# Trinket_TH_thru_parts_power_breakout.net
KiCad netlist of a schematic drawn in EAGLE
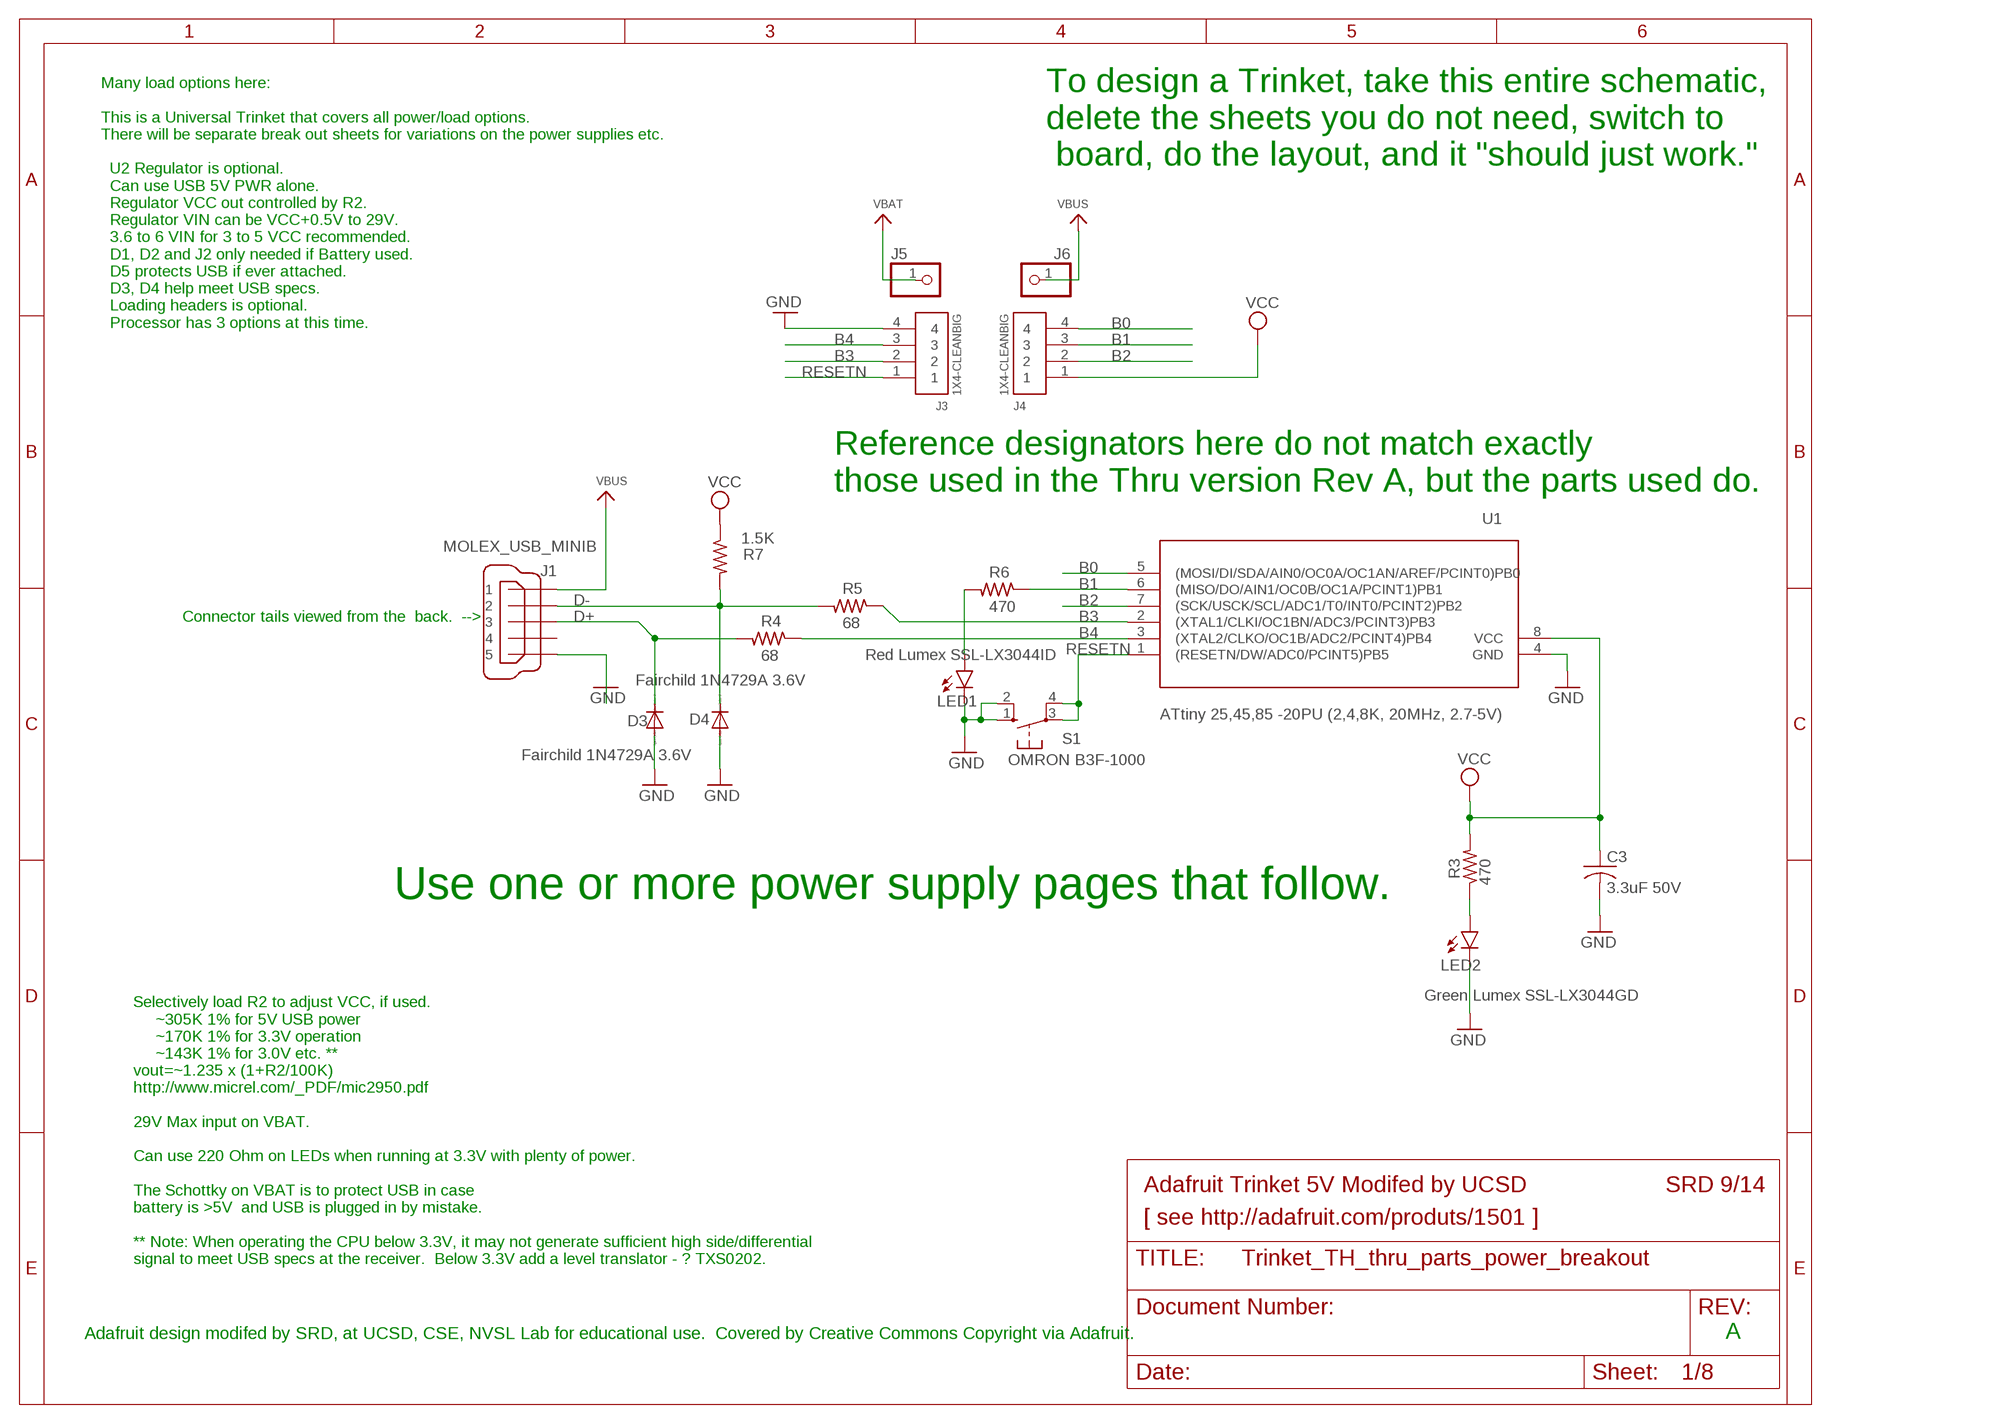
[diagram p0: schematic, sheet 1]
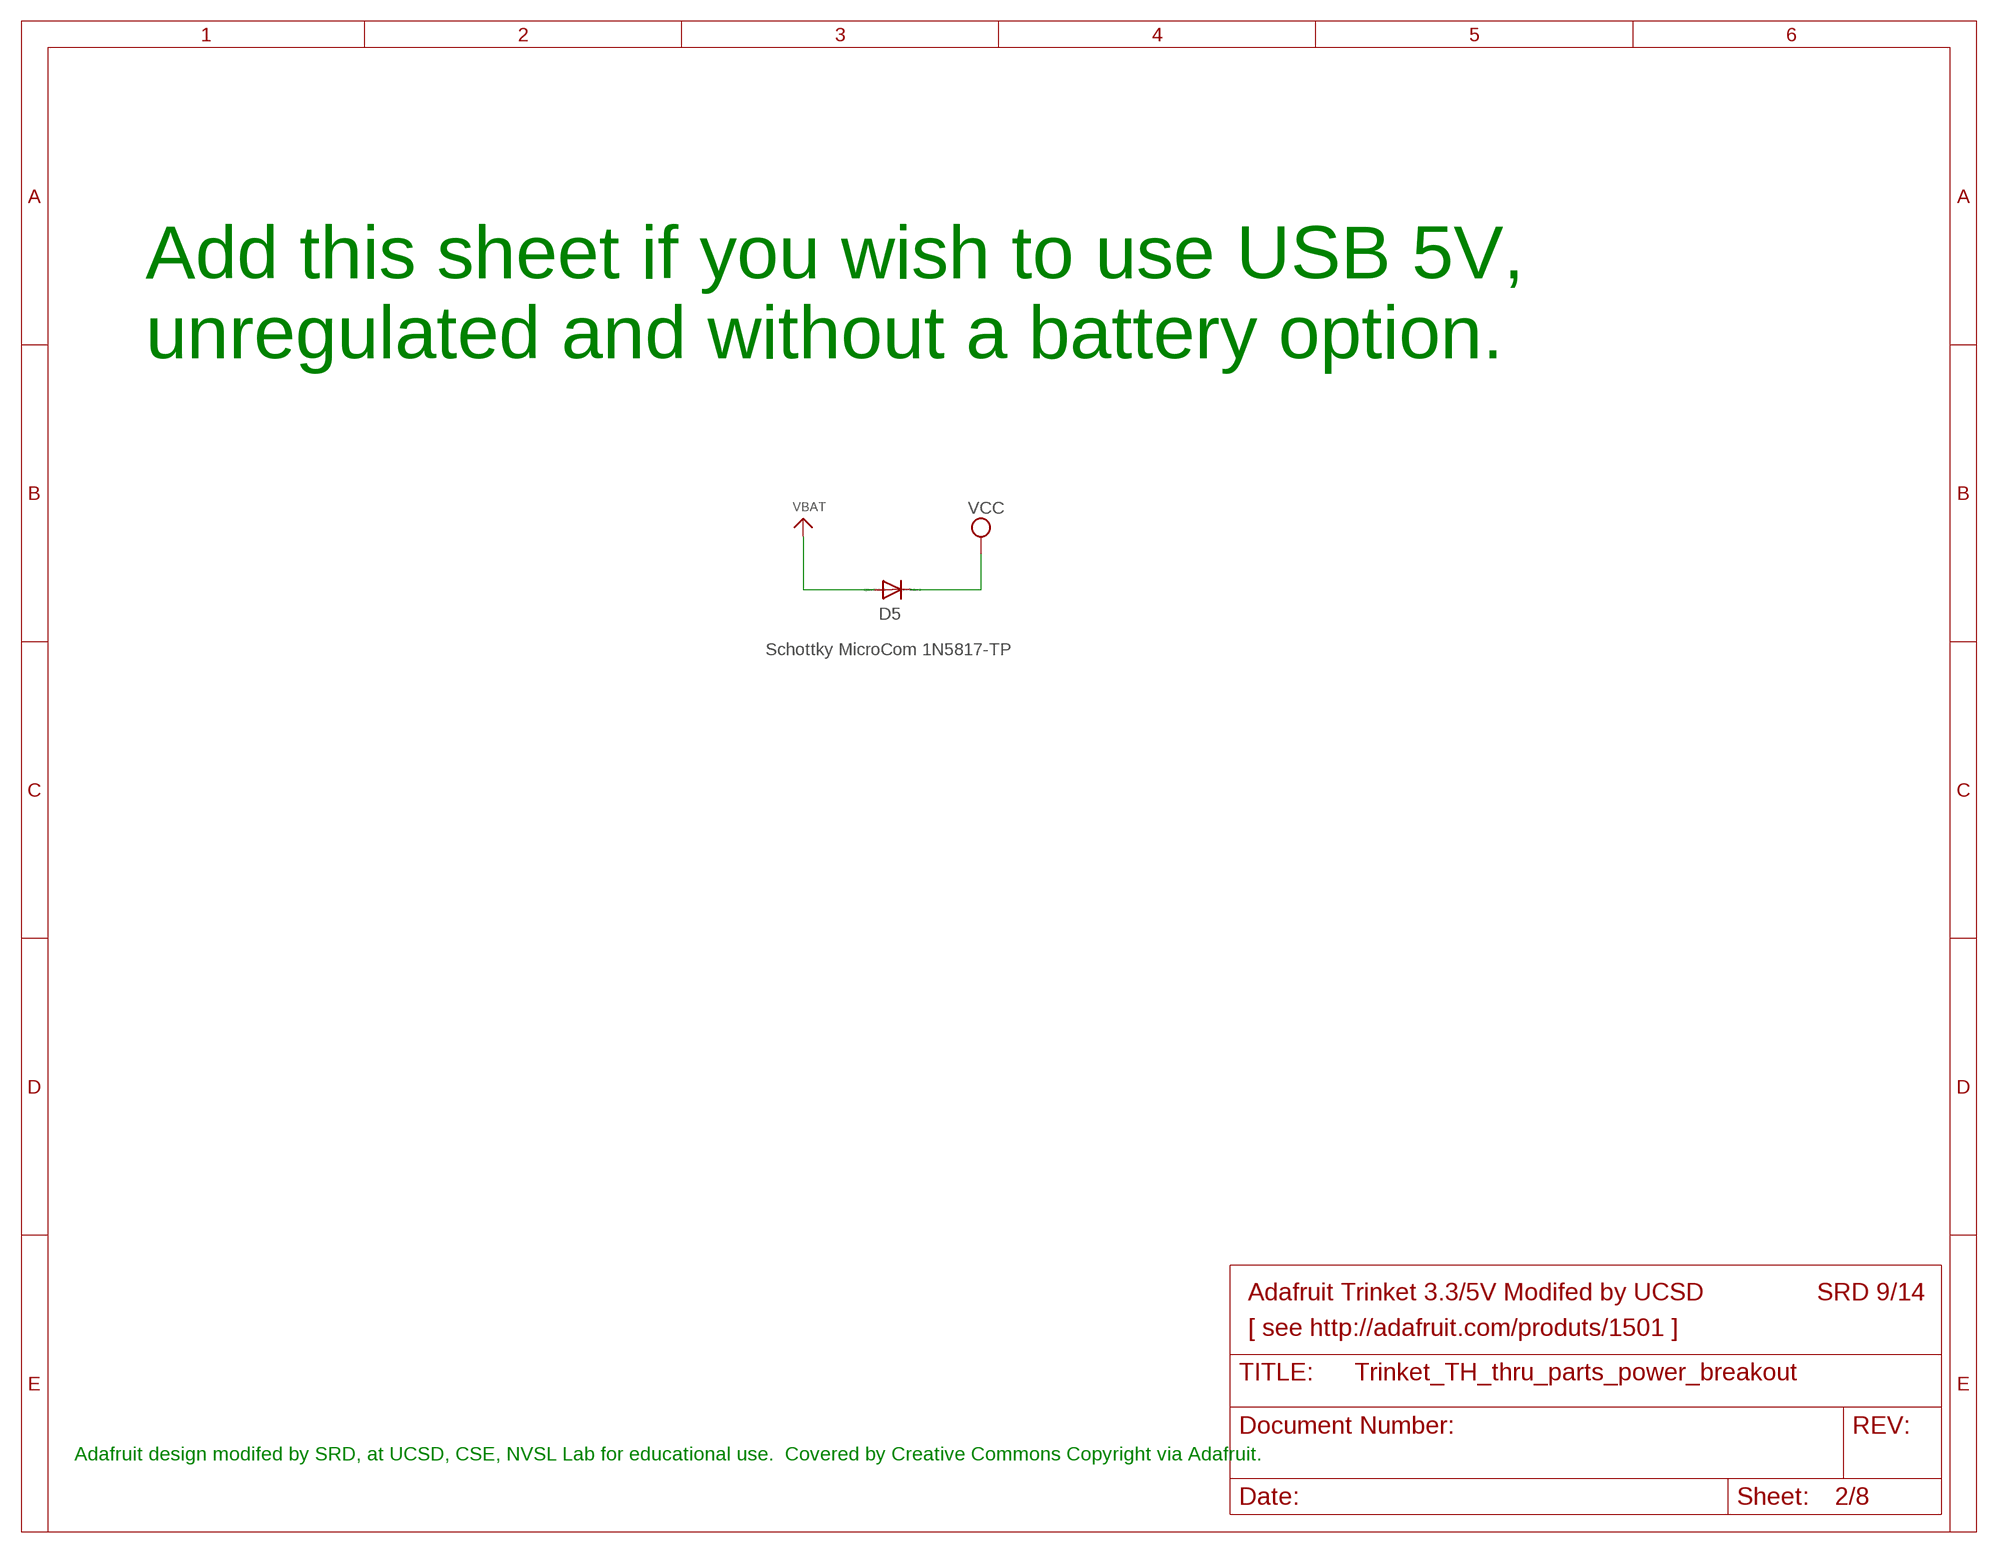
[diagram p1: schematic, sheet 2]
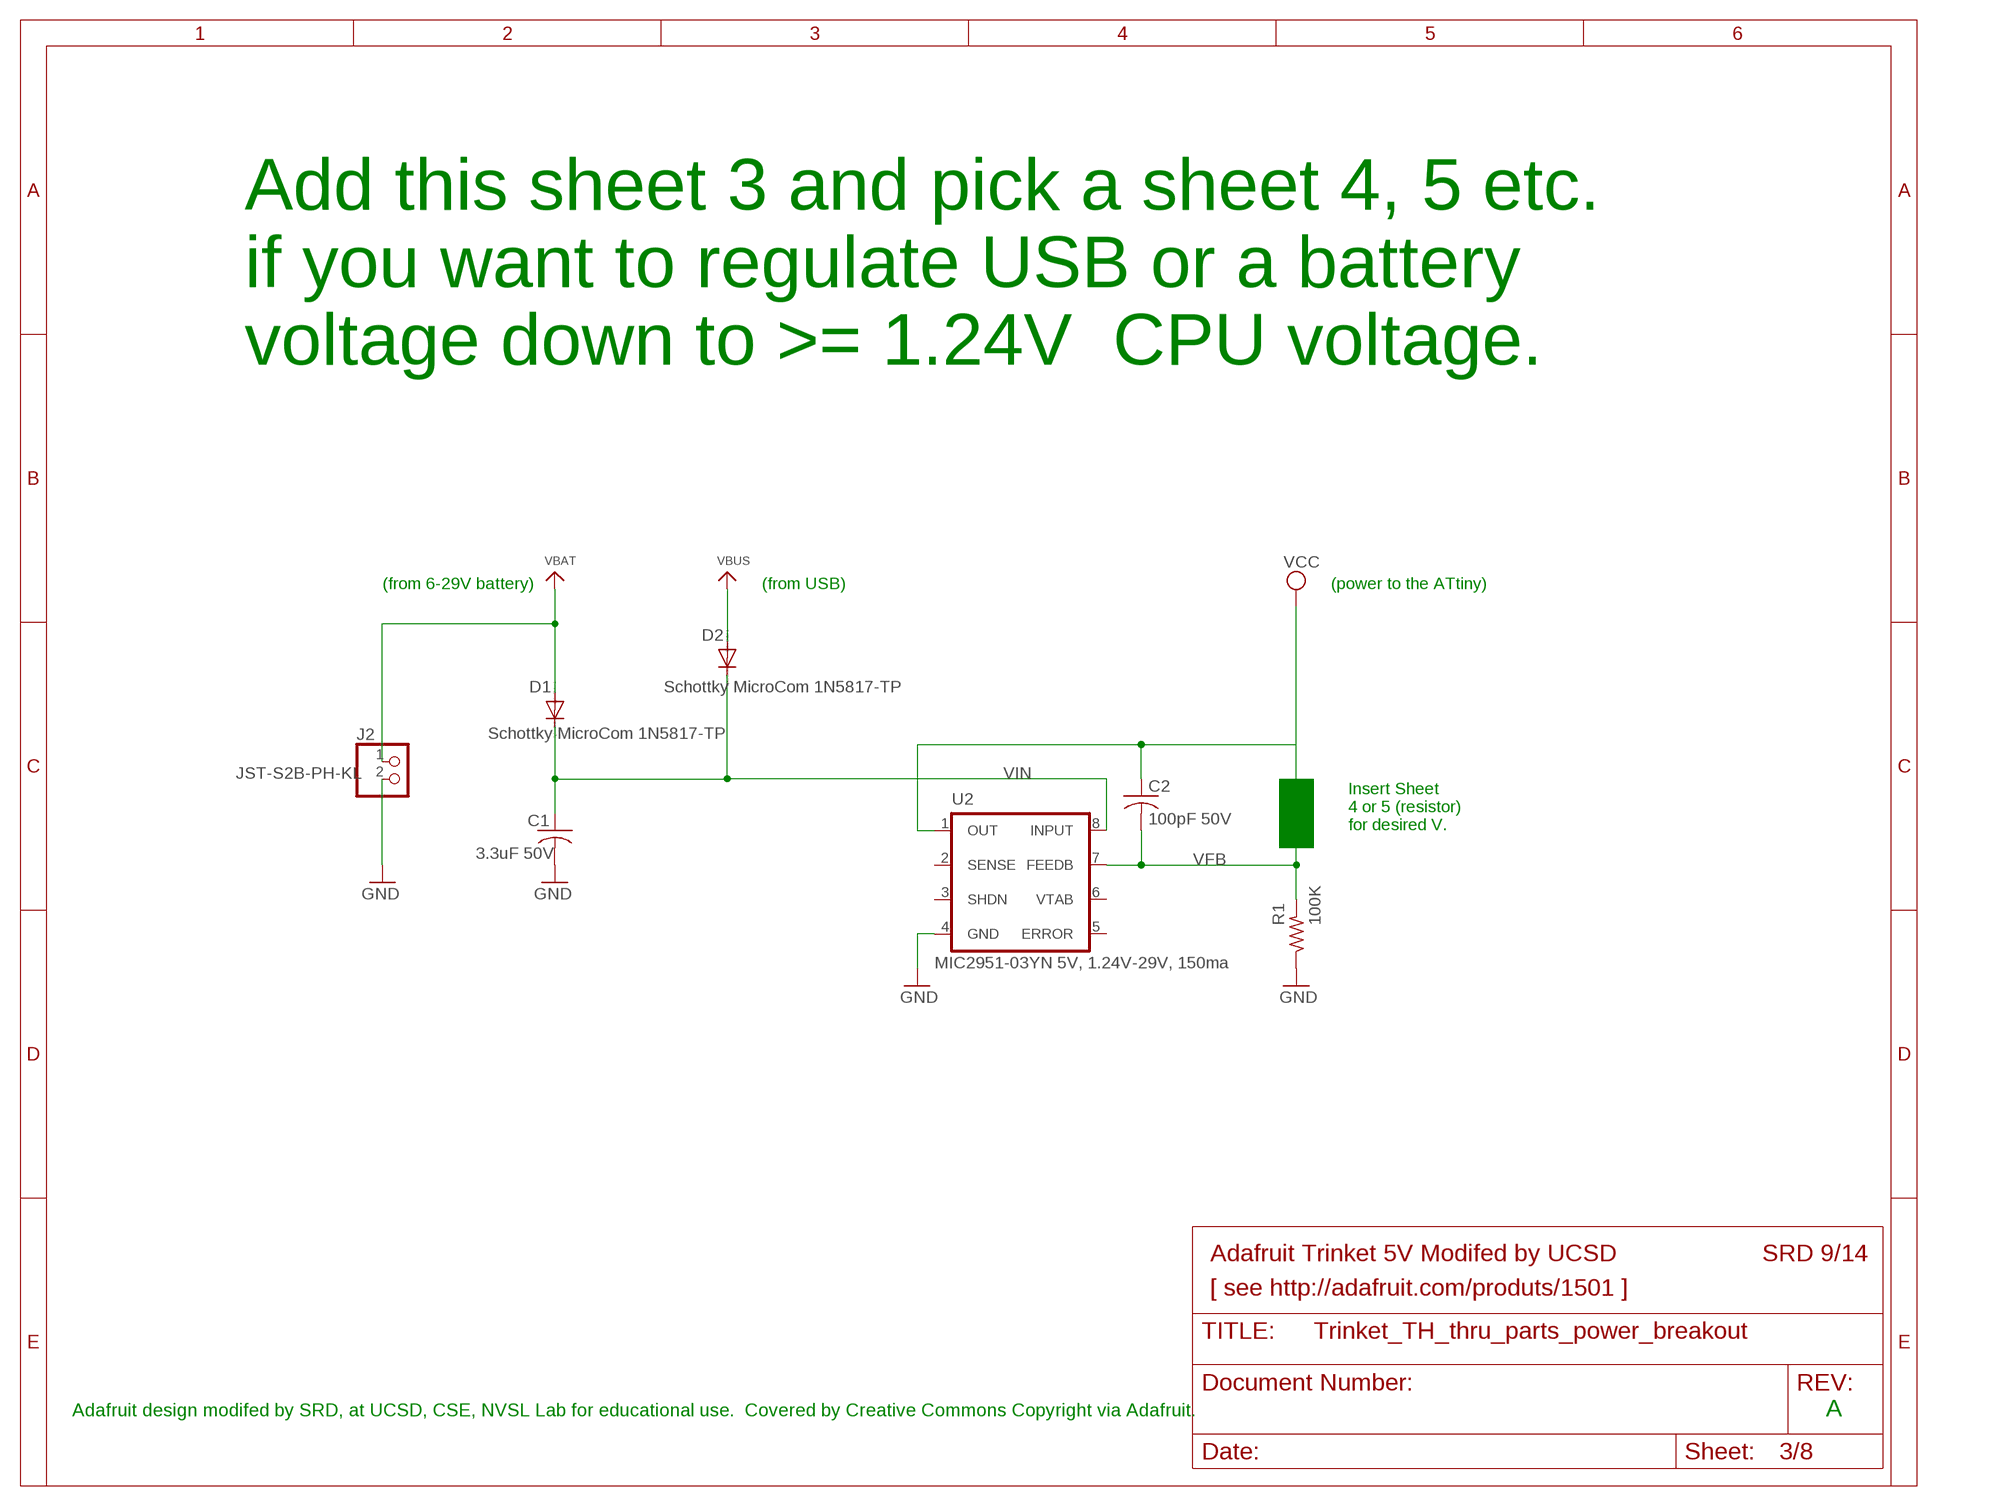
[diagram p2: schematic, sheet 3]
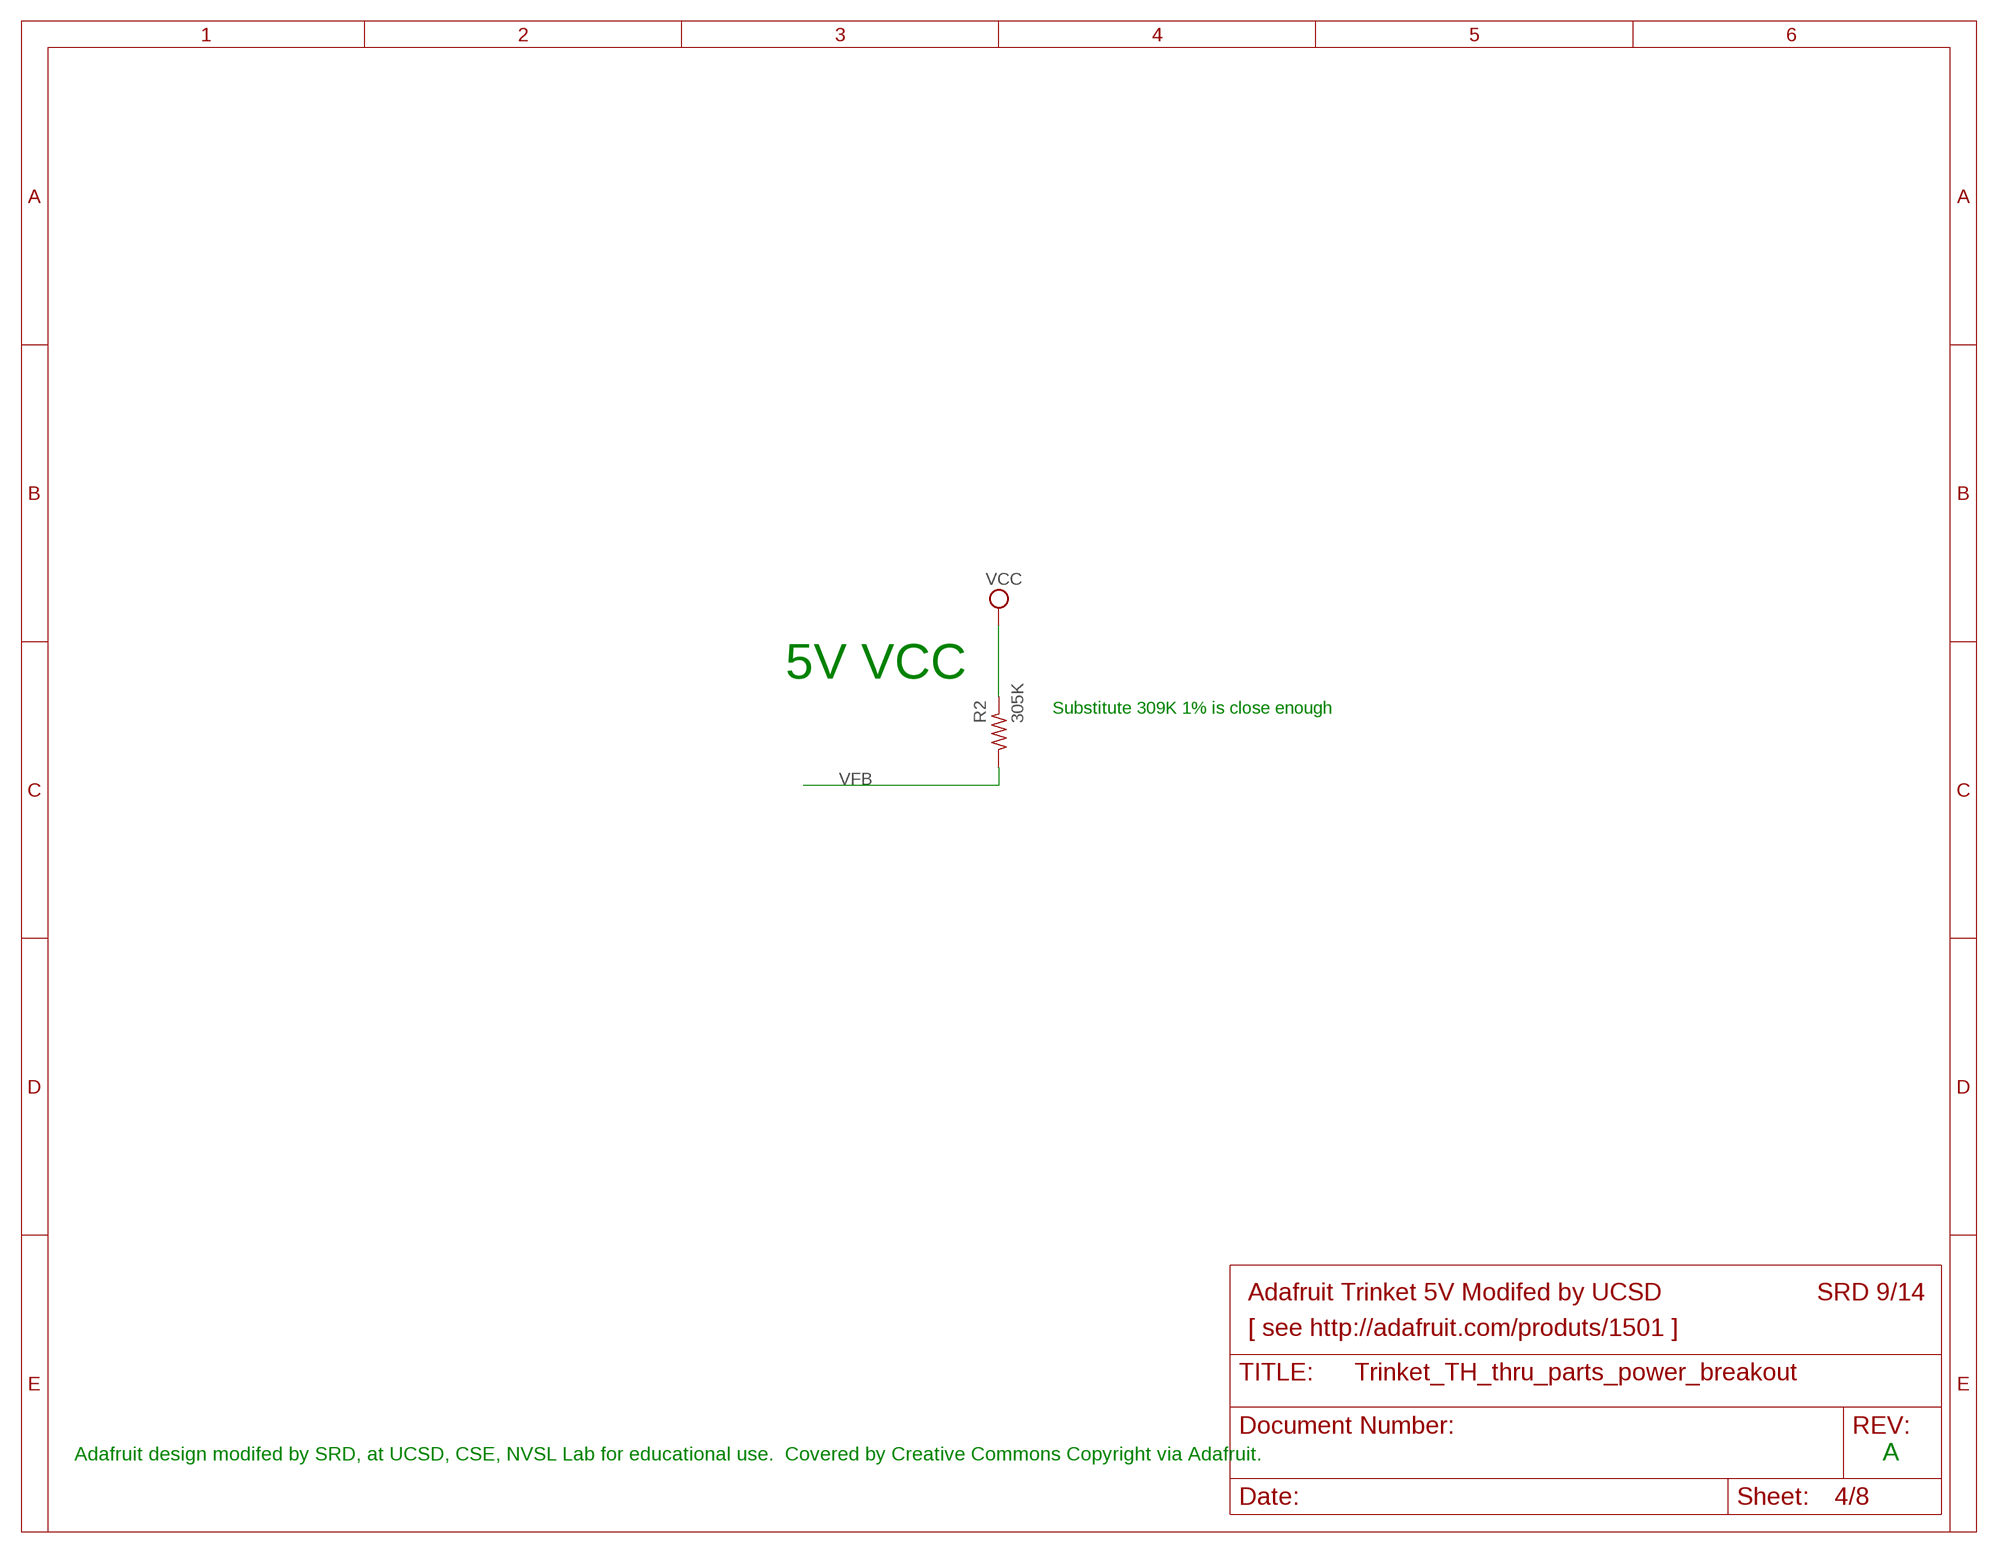
[diagram p3: schematic, sheet 4]
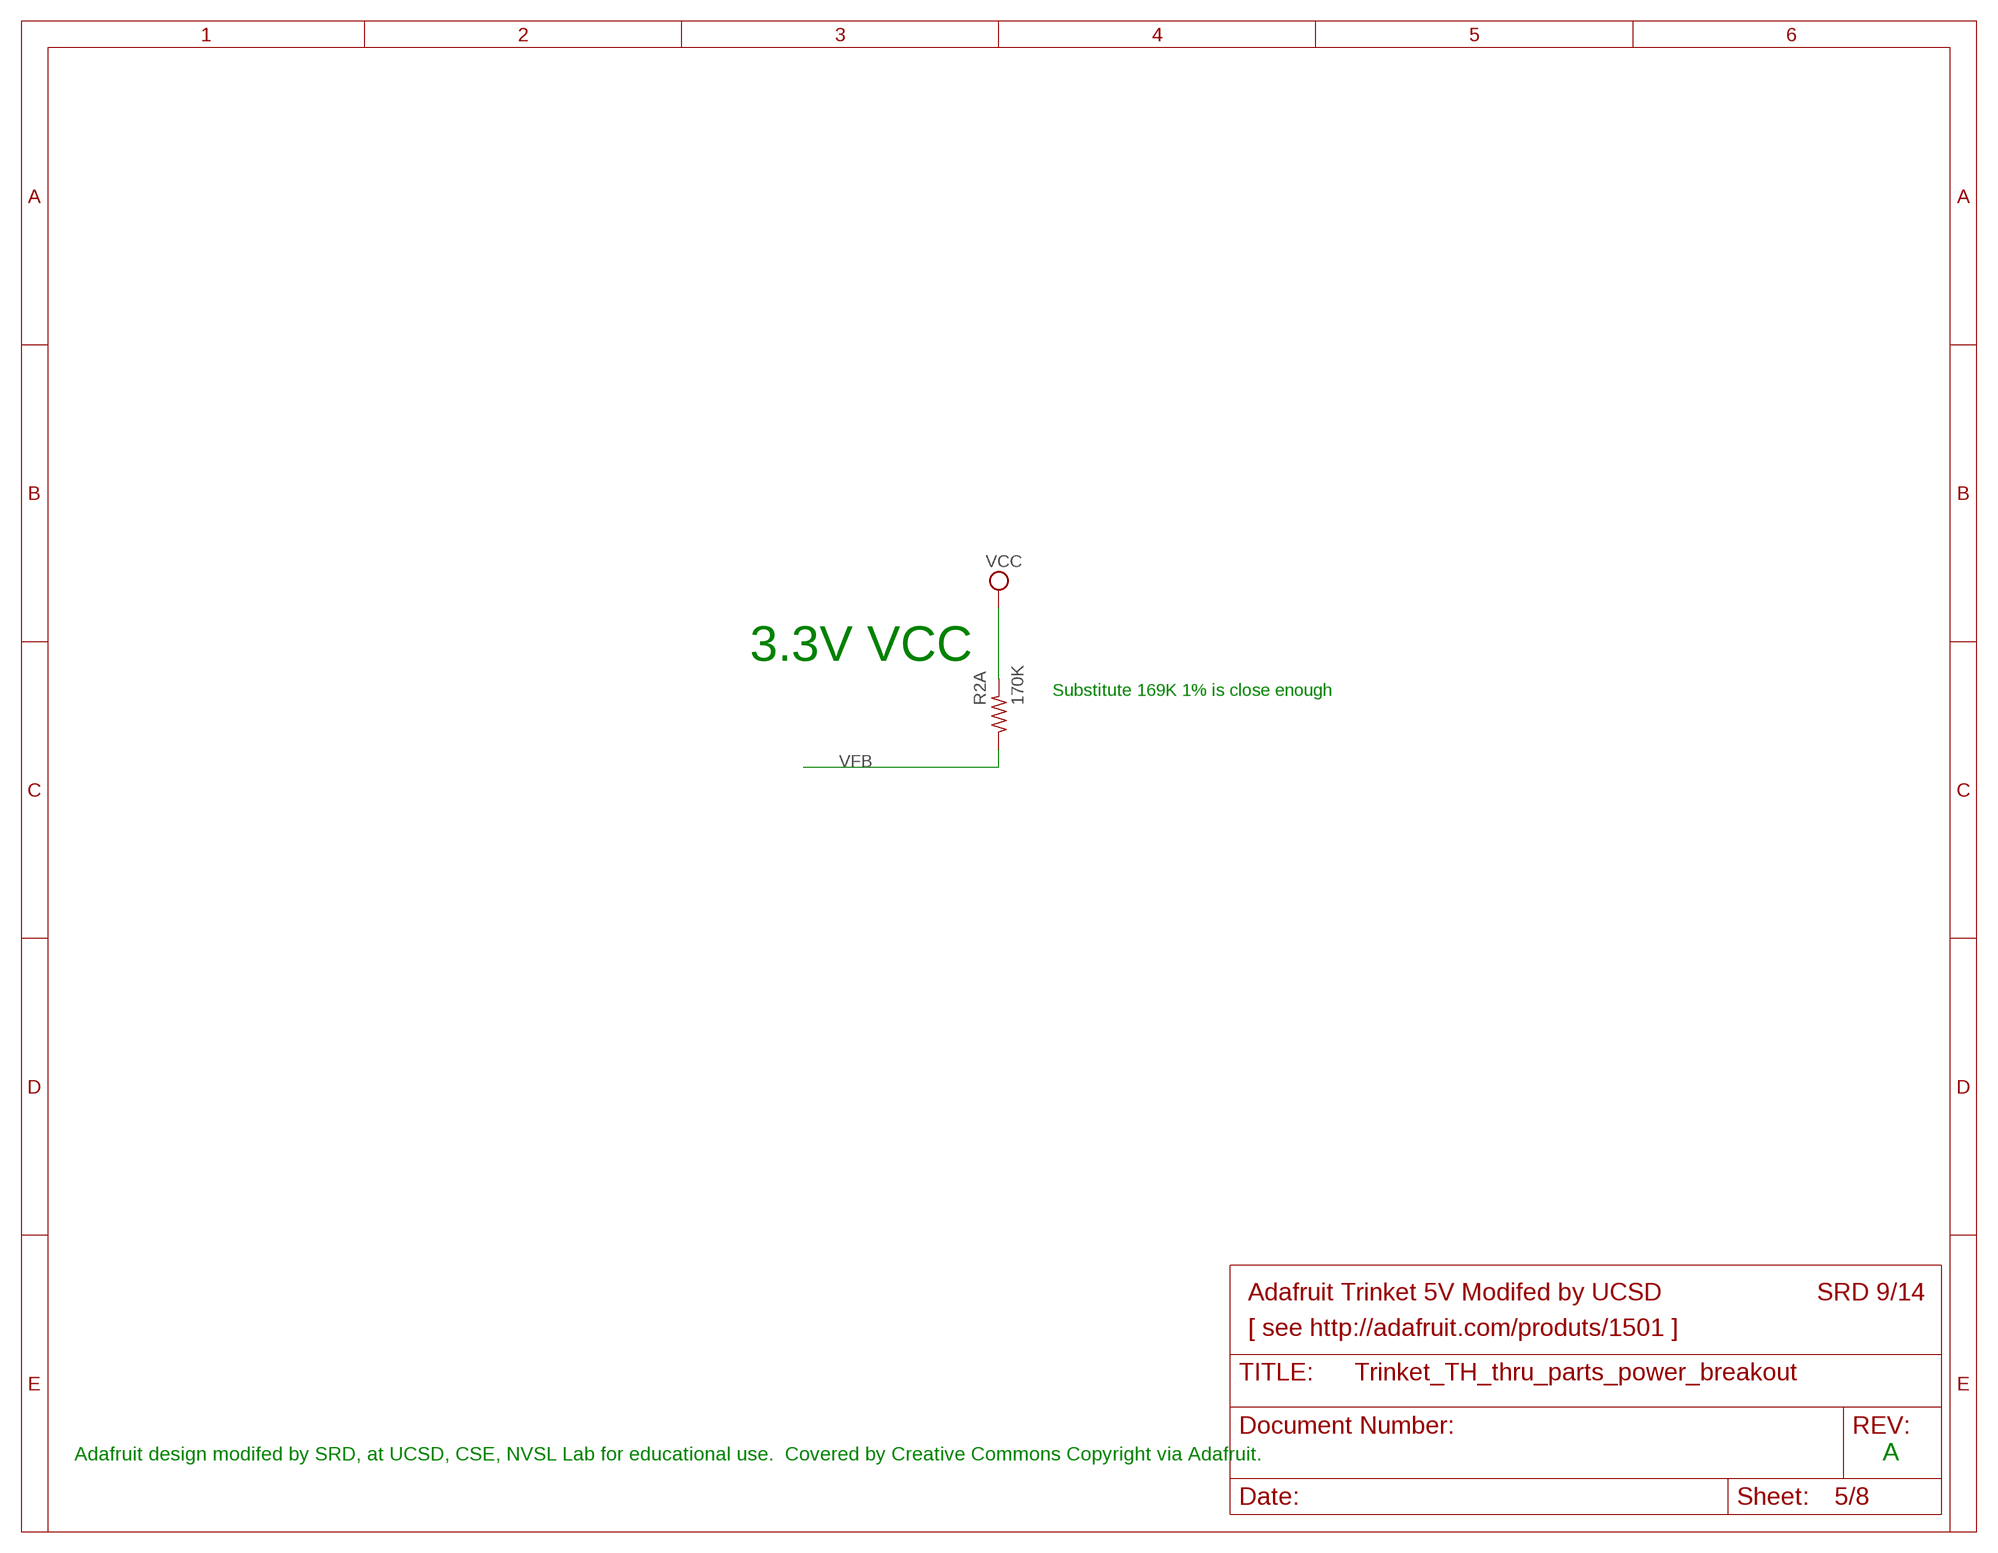
[diagram p4: schematic, sheet 5]
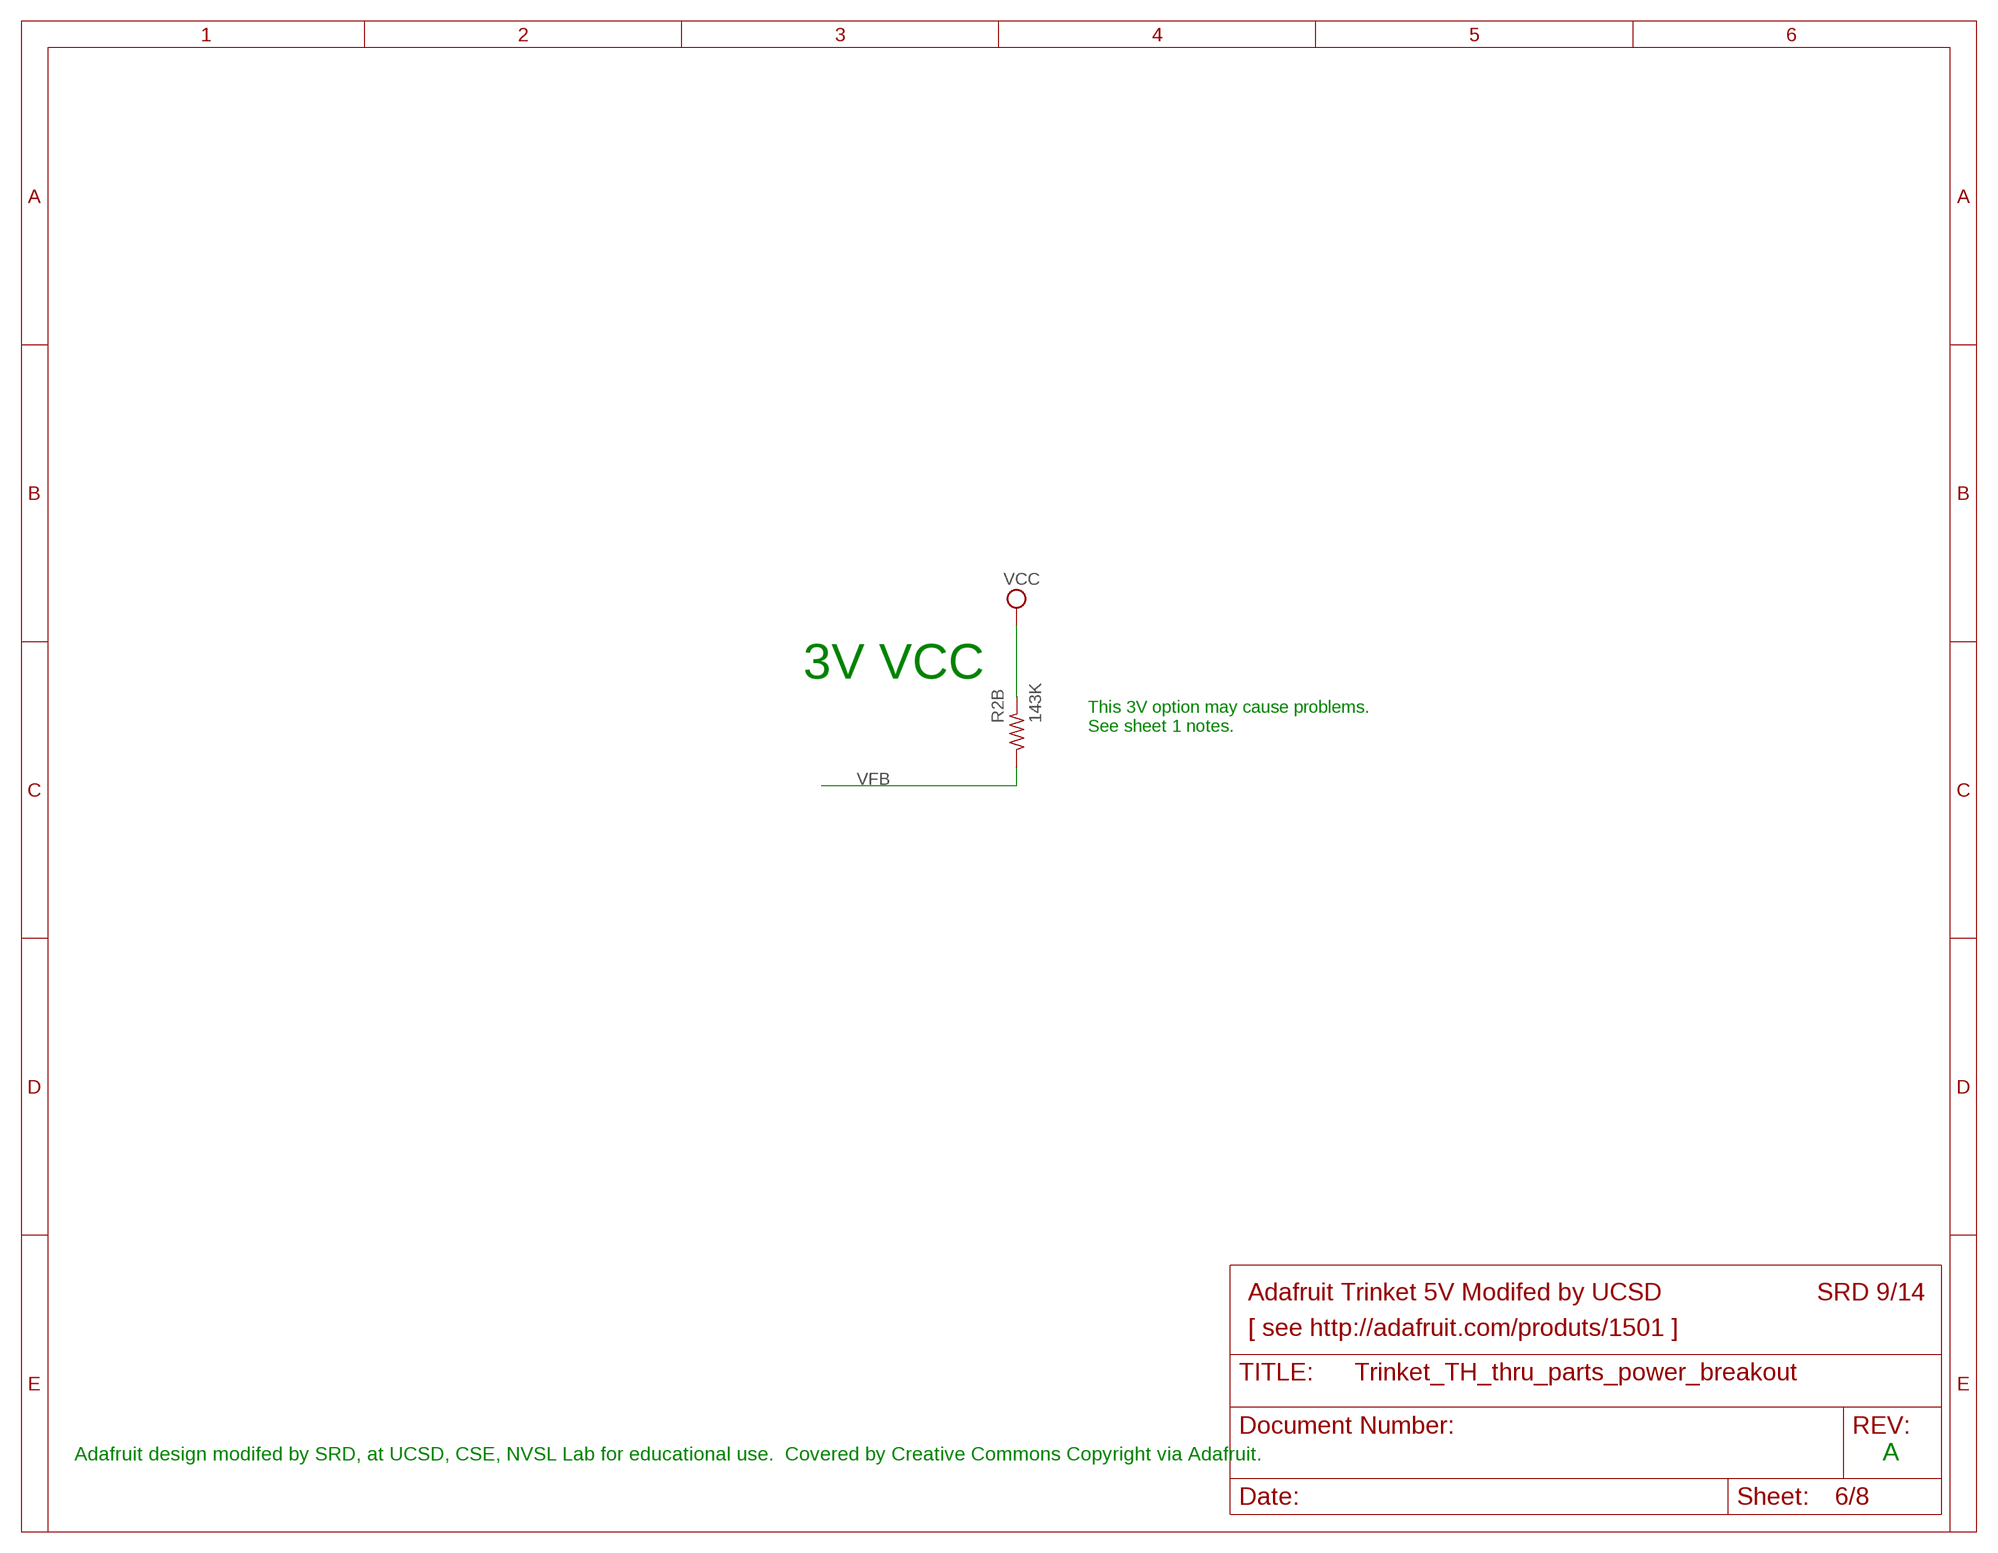
[diagram p5: schematic, sheet 6]
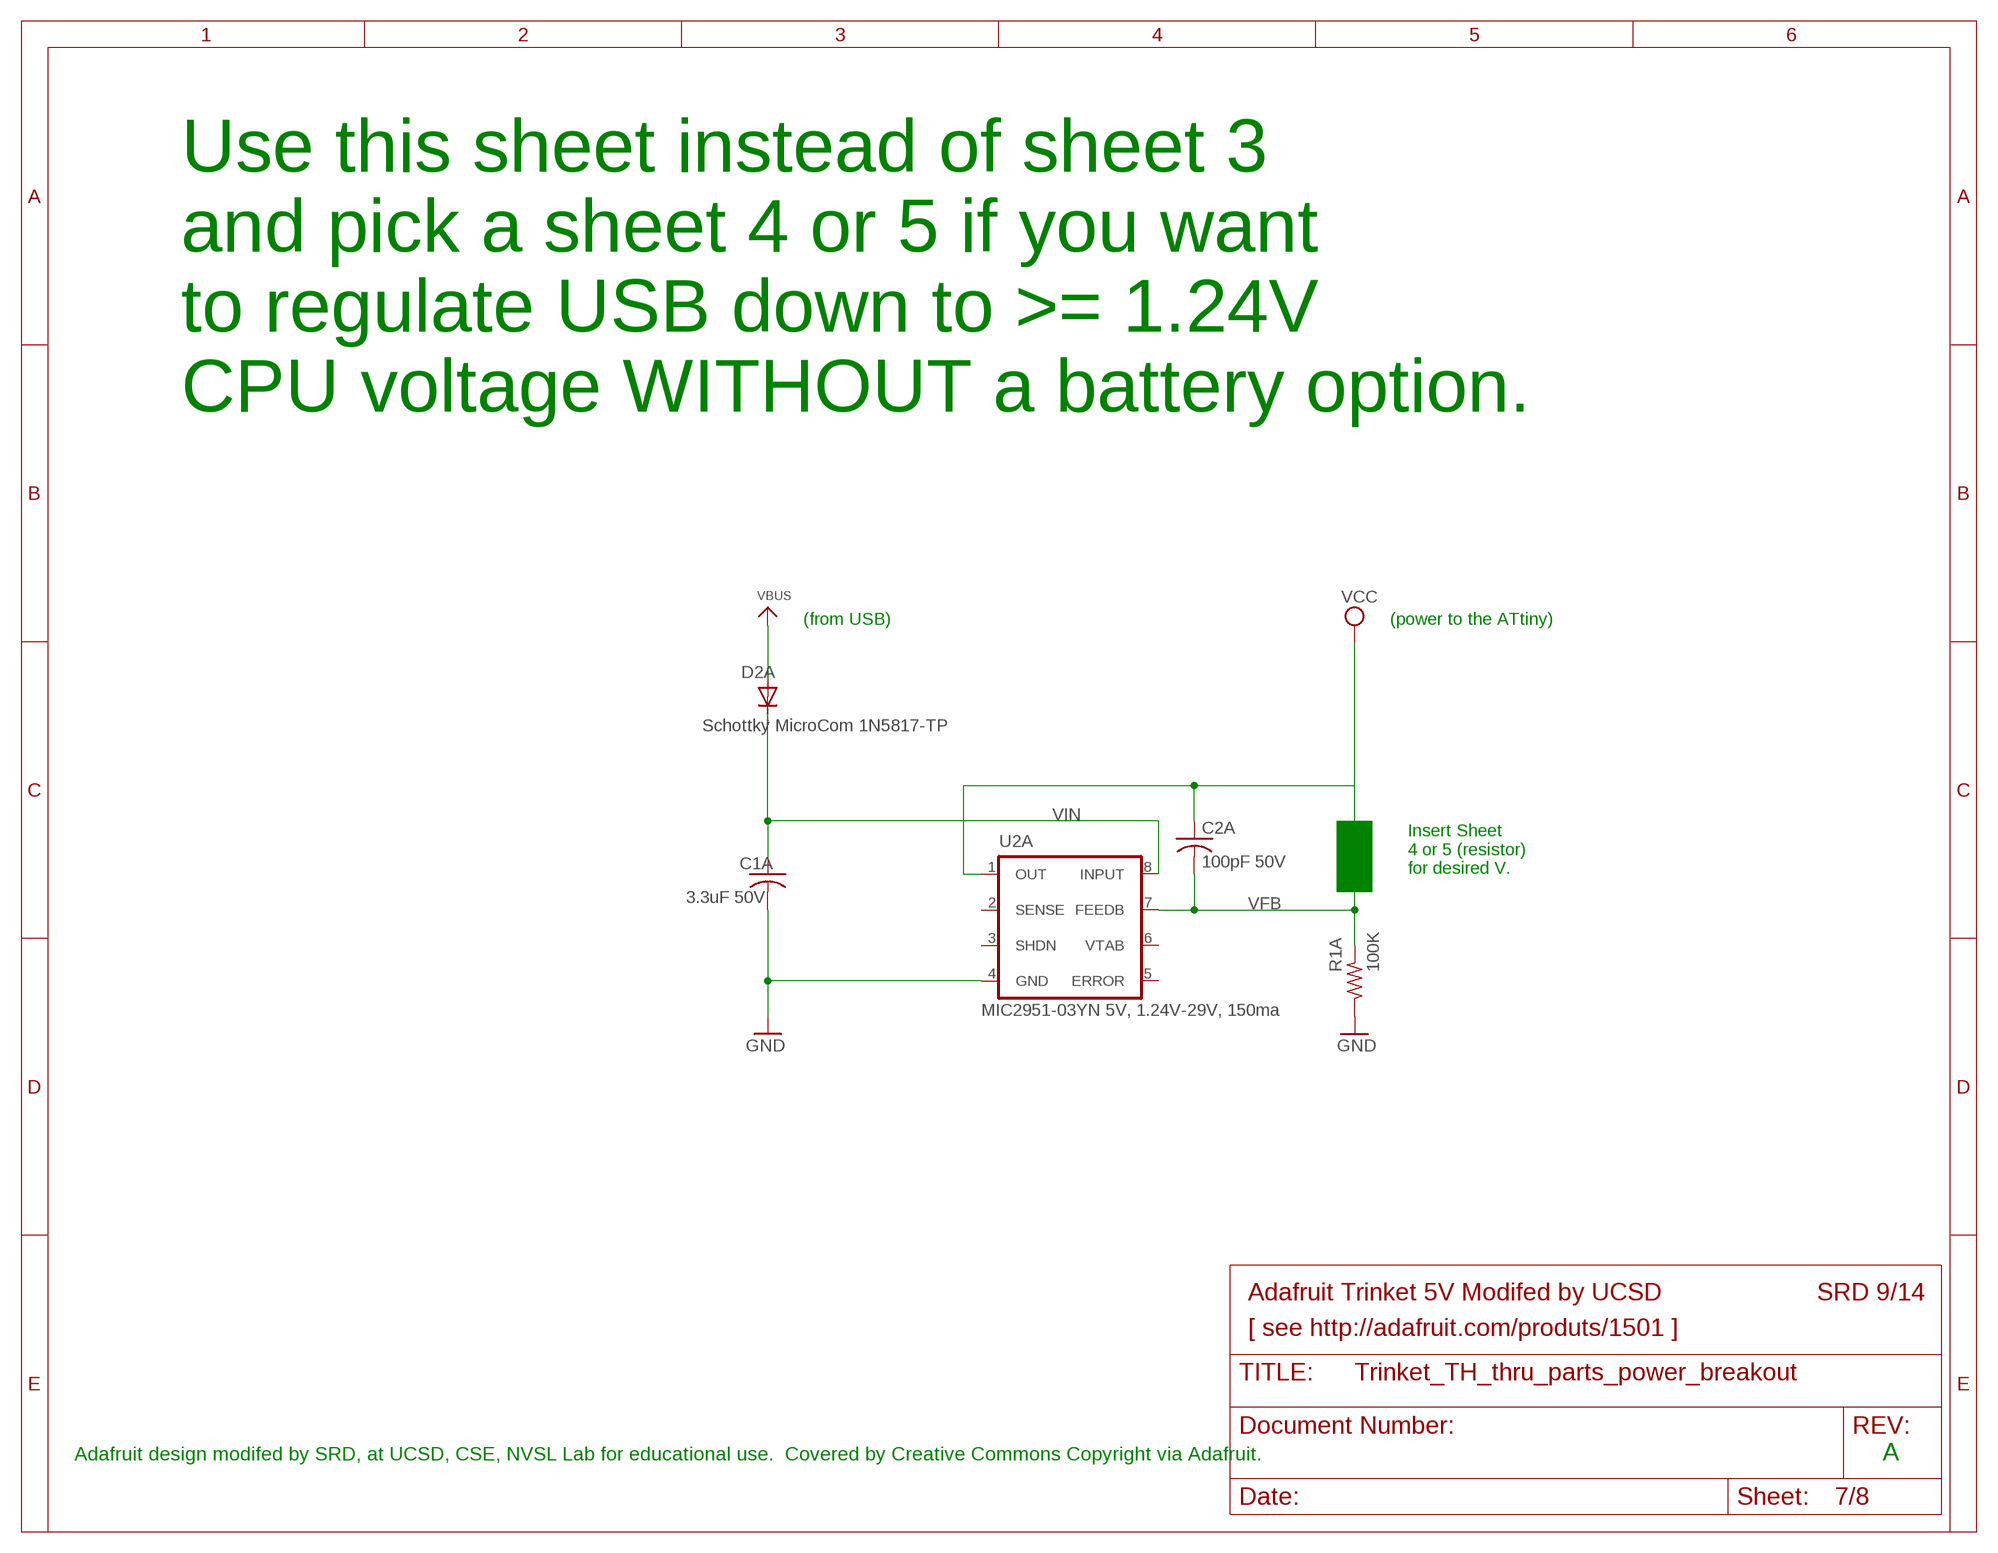
[diagram p6: schematic, sheet 7]
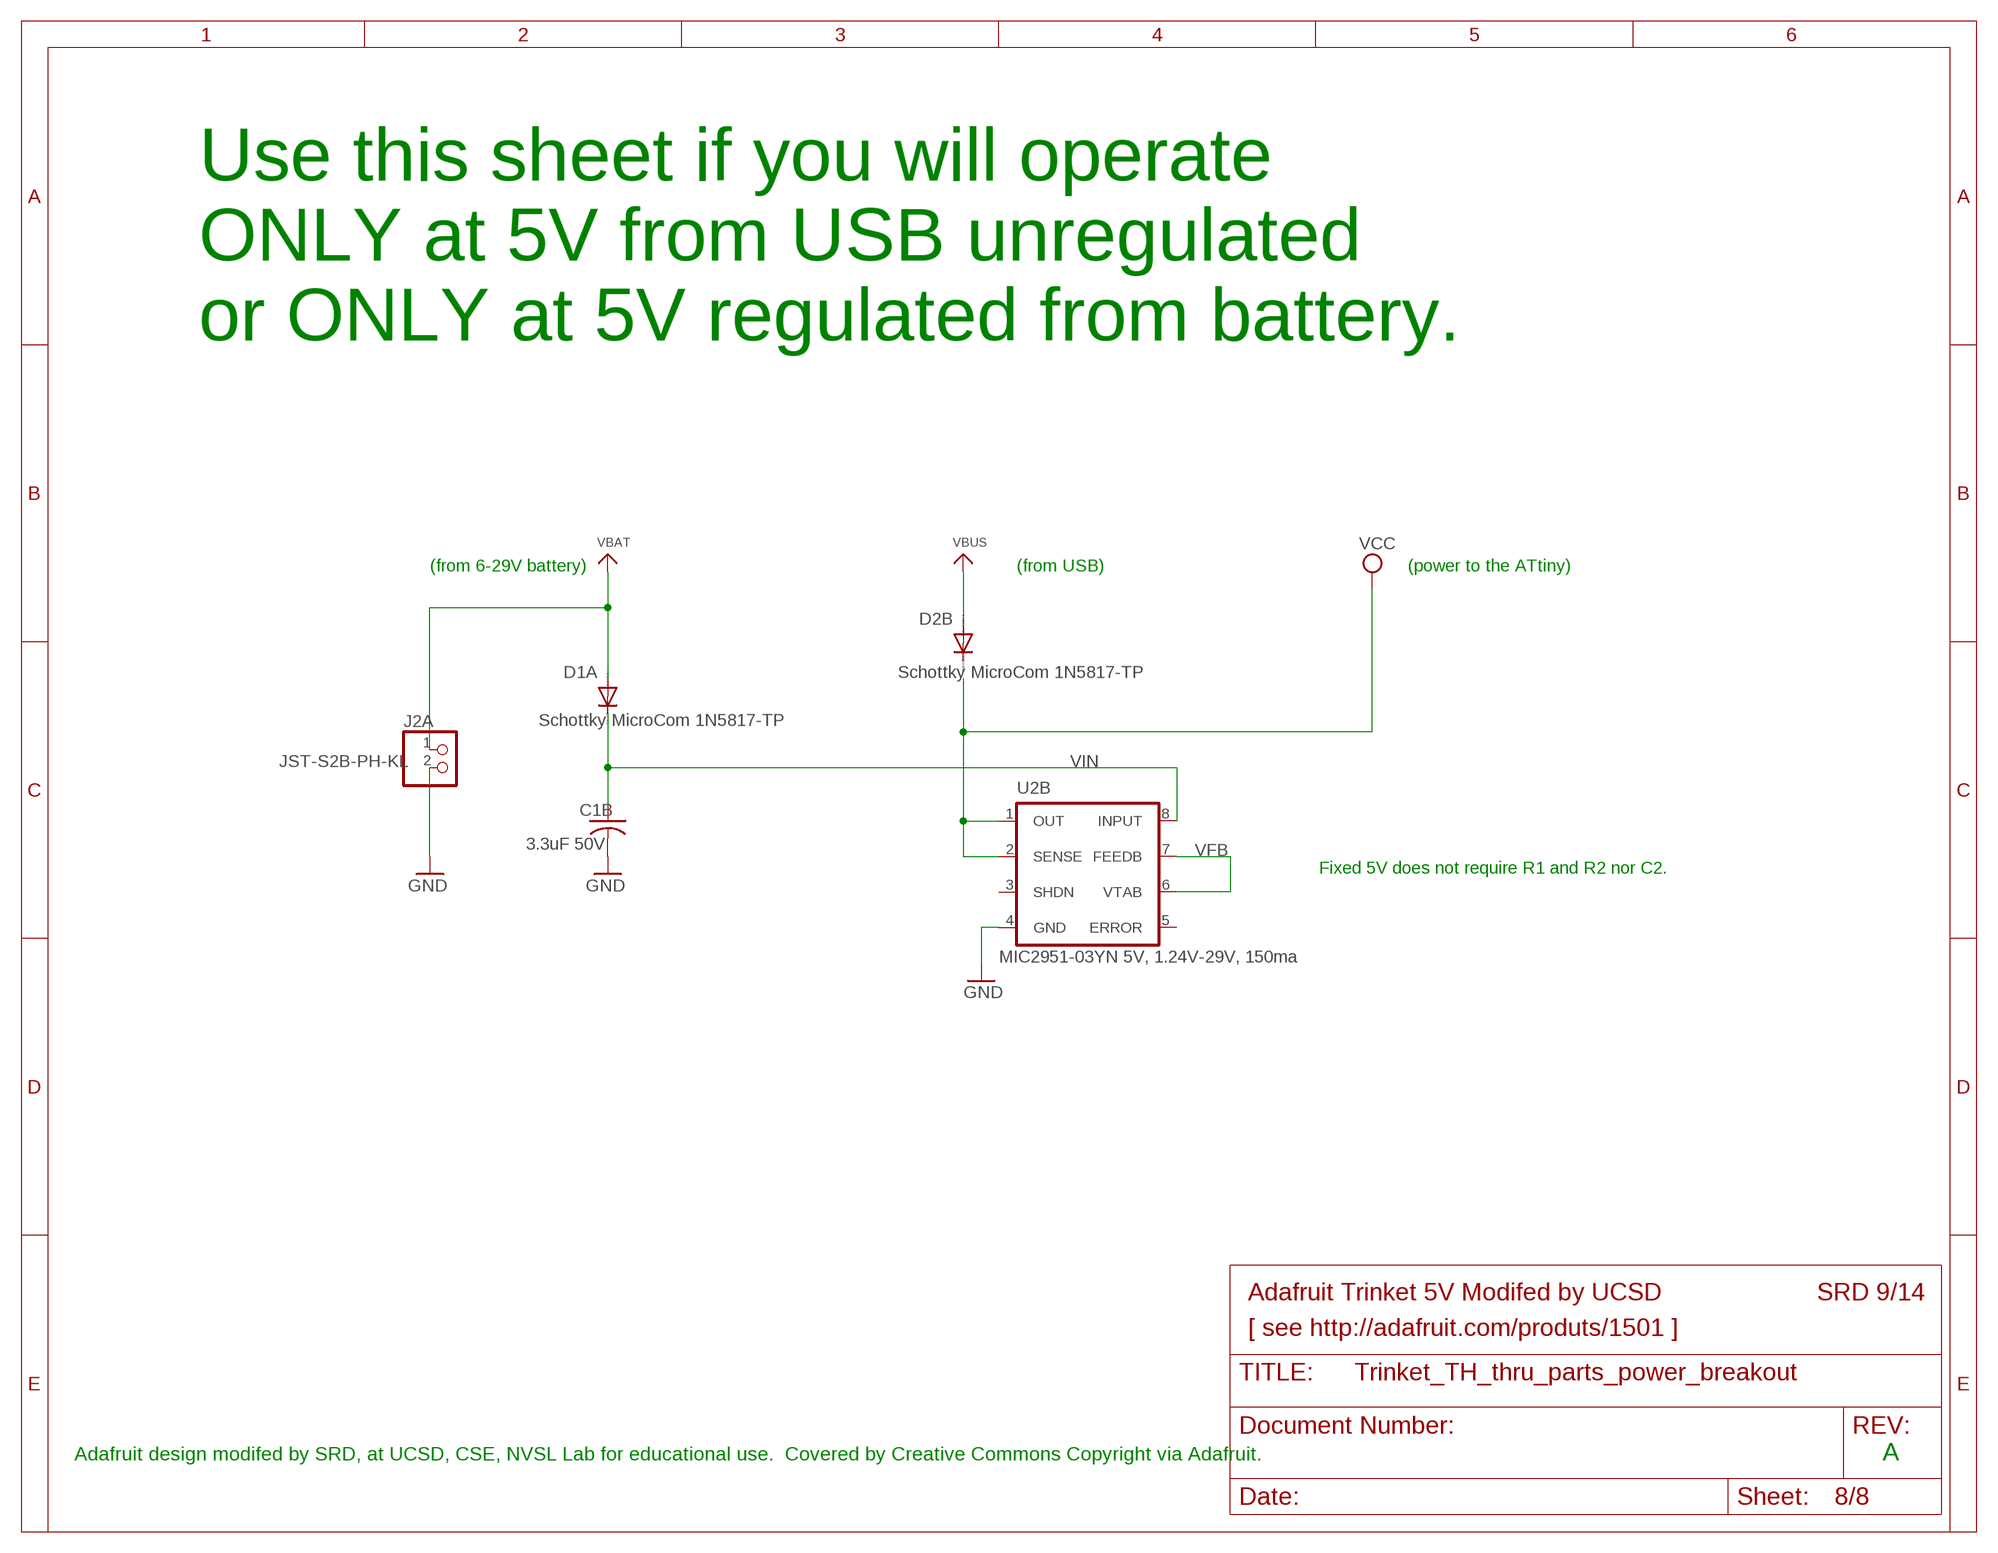
[diagram p7: schematic, sheet 8]

(export (version "E")
  (design (tool "Eeschema 10.0.6"))
  (components
    (comp (ref "C3")
      (value "3.3uF 50V")
      (footprint "eagle-import:C050-025X075")
      (fields (field (name "MFR") "TDK") (field (name "PARTNO") "FK20X7R1H335K"))
      (libsource (lib "eagle-import") (part "C-US050-025X075"))
    )
    (comp (ref "D3")
      (value "Fairchild 1N4729A 3.6V")
      (footprint "eagle-import:DO41-7.6")
      (fields (field (name "MFR") "Fairchild") (field (name "PARTNO") "1N4729A"))
      (libsource (lib "eagle-import") (part "DIODE-DO41-7.6"))
    )
    (comp (ref "D4")
      (value "Fairchild 1N4729A 3.6V")
      (footprint "eagle-import:DO41-7.6")
      (fields (field (name "MFR") "Fairchild") (field (name "PARTNO") "1N4729A"))
      (libsource (lib "eagle-import") (part "DIODE-DO41-7.6"))
    )
    (comp (ref "J1")
      (value "MOLEX_USB_MINIB")
      (footprint "eagle-import:32005-601-ROUND")
      (fields (field (name "MFR") "Molex") (field (name "PARTNO") "0548190519"))
      (libsource (lib "eagle-import") (part "MOLEX_USB_MINIB"))
    )
    (comp (ref "J3")
      (value "1X4-CLEANBIG")
      (footprint "eagle-import:1X04-CLEANBIG")
      (libsource (lib "eagle-import") (part "1X4-CLEANBIG"))
    )
    (comp (ref "J4")
      (value "1X4-CLEANBIG")
      (footprint "eagle-import:1X04-CLEANBIG")
      (libsource (lib "eagle-import") (part "1X4-CLEANBIG"))
    )
    (comp (ref "J5")
      (value "PINHD-1X1CB")
      (footprint "eagle-import:1X01-CLEANBIG")
      (libsource (lib "eagle-import") (part "PINHD-1X1CB"))
    )
    (comp (ref "J6")
      (value "PINHD-1X1CB")
      (footprint "eagle-import:1X01-CLEANBIG")
      (libsource (lib "eagle-import") (part "PINHD-1X1CB"))
    )
    (comp (ref "LED1")
      (value "Red Lumex SSL-LX3044ID")
      (footprint "eagle-import:LED3MM")
      (fields (field (name "MFR") "Lumex") (field (name "PARTNO") "SSL-LX3044ID"))
      (libsource (lib "eagle-import") (part "LED3MM"))
    )
    (comp (ref "LED2")
      (value "Green Lumex SSL-LX3044GD")
      (footprint "eagle-import:LED3MM")
      (fields (field (name "MFR") "Lumex") (field (name "PARTNO") "SSL-LX3044GD"))
      (libsource (lib "eagle-import") (part "LED3MM"))
    )
    (comp (ref "R3")
      (value "470")
      (footprint "eagle-import:0204_7")
      (fields (field (name "MFR") "Yageo") (field (name "PARTNO") "CFR-12JB-52-470R"))
      (libsource (lib "eagle-import") (part "R-US_0204/7"))
    )
    (comp (ref "R4")
      (value "68")
      (footprint "eagle-import:0204_7")
      (fields (field (name "MFR") "Yageo") (field (name "PARTNO") "CFR-12JB-52-68R"))
      (libsource (lib "eagle-import") (part "R-US_0204/7"))
    )
    (comp (ref "R5")
      (value "68")
      (footprint "eagle-import:0204_7")
      (fields (field (name "MFR") "Yageo") (field (name "PARTNO") "CFR-12JB-52-68R"))
      (libsource (lib "eagle-import") (part "R-US_0204/7"))
    )
    (comp (ref "R6")
      (value "470")
      (footprint "eagle-import:0204_7")
      (fields (field (name "MFR") "Yageo") (field (name "PARTNO") "CFR-12JB-52-470R"))
      (libsource (lib "eagle-import") (part "R-US_0204/7"))
    )
    (comp (ref "R7")
      (value "1.5K")
      (footprint "eagle-import:0204_7")
      (fields (field (name "MFR") "Yageo") (field (name "PARTNO") "CFR-12JB-52-1K5"))
      (libsource (lib "eagle-import") (part "R-US_0204/7"))
    )
    (comp (ref "S1")
      (value "OMRON B3F-1000")
      (footprint "eagle-import:B3F-10XX")
      (fields (field (name "MPN") "B3F-1000") (field (name "MFR") "Omron"))
      (libsource (lib "eagle-import") (part "10-XX"))
    )
    (comp (ref "U1")
      (value "ATtiny 25,45,85 -20PU (2,4,8K, 20MHz, 2.7-5V)")
      (footprint "eagle-import:DIL08")
      (fields (field (name "MFR") "Atmel") (field (name "PARTNO") "ATTINY85-20PU-ND"))
      (libsource (lib "eagle-import") (part "ATTINY85P-20"))
    )
    (comp (ref "C1")
      (value "3.3uF 50V")
      (footprint "eagle-import:C050-025X075")
      (fields (field (name "MFR") "TDK") (field (name "PARTNO") "FK20X7R1H335K"))
      (libsource (lib "eagle-import") (part "C-US050-025X075"))
    )
    (comp (ref "C2")
      (value "100pF 50V")
      (footprint "eagle-import:C050-025X075")
      (fields (field (name "MFR") "TDK") (field (name "PARTNO") "FK28C0G1H101J"))
      (libsource (lib "eagle-import") (part "C-US050-025X075"))
    )
    (comp (ref "D1")
      (value "Schottky MicroCom 1N5817-TP")
      (footprint "eagle-import:DO41-7.6")
      (fields (field (name "MFR") "Micro Com.") (field (name "PARTNO") "1N5817-TP"))
      (libsource (lib "eagle-import") (part "DIODE-DO41-7.6"))
    )
    (comp (ref "D2")
      (value "Schottky MicroCom 1N5817-TP")
      (footprint "eagle-import:DO41-7.6")
      (fields (field (name "MFR") "Micro Com.") (field (name "PARTNO") "1N5817-TP"))
      (libsource (lib "eagle-import") (part "DIODE-DO41-7.6"))
    )
    (comp (ref "J2")
      (value "JST-S2B-PH-KL")
      (footprint "eagle-import:JST_S2B_PH_KL")
      (fields (field (name "MFR") "JST") (field (name "PARTNO") "JST_S2B_PH_KL"))
      (libsource (lib "eagle-import") (part "CON_JST_PH_2PINJST_S2B_PH_KL"))
    )
    (comp (ref "R1")
      (value "100K")
      (footprint "eagle-import:0204_7")
      (fields (field (name "MFR") "Yageo") (field (name "PARTNO") "MFR-25FBF52-100K"))
      (libsource (lib "eagle-import") (part "R-US_0204/7"))
    )
    (comp (ref "U2")
      (value "MIC2951-03YN 5V, 1.24V-29V, 150ma")
      (footprint "eagle-import:DIL08")
      (fields (field (name "MFR") "Micrel") (field (name "PARTNO") "MIC2951-03YN"))
      (libsource (lib "eagle-import") (part "MIC2951-03YNCN"))
    )
    (comp (ref "D5")
      (value "Schottky MicroCom 1N5817-TP")
      (footprint "eagle-import:DO41-7.6")
      (fields (field (name "MFR") "Micro Com.") (field (name "PARTNO") "1N5817-TP"))
      (libsource (lib "eagle-import") (part "DIODE-DO41-7.6"))
    )
    (comp (ref "R2B")
      (value "143K")
      (footprint "eagle-import:0204_7")
      (fields (field (name "MFR") "Yageo") (field (name "PARTNO") "MFR-25FBF52-143K"))
      (libsource (lib "eagle-import") (part "R-US_0204/7"))
    )
    (comp (ref "R2")
      (value "305K")
      (footprint "eagle-import:0204_7")
      (fields (field (name "MFR") "Yageo") (field (name "PARTNO") "MFR-25FBF52-301K"))
      (libsource (lib "eagle-import") (part "R-US_0204/7"))
    )
    (comp (ref "C1A")
      (value "3.3uF 50V")
      (footprint "eagle-import:C050-025X075")
      (fields (field (name "MFR") "TDK") (field (name "PARTNO") "FK20X7R1H335K"))
      (libsource (lib "eagle-import") (part "C-US050-025X075"))
    )
    (comp (ref "C2A")
      (value "100pF 50V")
      (footprint "eagle-import:C050-025X075")
      (fields (field (name "MFR") "TDK") (field (name "PARTNO") "FK28C0G1H101J"))
      (libsource (lib "eagle-import") (part "C-US050-025X075"))
    )
    (comp (ref "D2A")
      (value "Schottky MicroCom 1N5817-TP")
      (footprint "eagle-import:DO41-7.6")
      (fields (field (name "MFR") "Micro Com.") (field (name "PARTNO") "1N5817-TP"))
      (libsource (lib "eagle-import") (part "DIODE-DO41-7.6"))
    )
    (comp (ref "R1A")
      (value "100K")
      (footprint "eagle-import:0204_7")
      (fields (field (name "MFR") "Yageo") (field (name "PARTNO") "MFR-25FBF52-100K"))
      (libsource (lib "eagle-import") (part "R-US_0204/7"))
    )
    (comp (ref "U2A")
      (value "MIC2951-03YN 5V, 1.24V-29V, 150ma")
      (footprint "eagle-import:DIL08")
      (fields (field (name "MFR") "Micrel") (field (name "PARTNO") "MIC2951-03YN"))
      (libsource (lib "eagle-import") (part "MIC2951-03YNCN"))
    )
    (comp (ref "C1B")
      (value "3.3uF 50V")
      (footprint "eagle-import:C050-025X075")
      (fields (field (name "MFR") "TDK") (field (name "PARTNO") "FK20X7R1H335K"))
      (libsource (lib "eagle-import") (part "C-US050-025X075"))
    )
    (comp (ref "D1A")
      (value "Schottky MicroCom 1N5817-TP")
      (footprint "eagle-import:DO41-7.6")
      (fields (field (name "MFR") "Micro Com.") (field (name "PARTNO") "1N5817-TP"))
      (libsource (lib "eagle-import") (part "DIODE-DO41-7.6"))
    )
    (comp (ref "D2B")
      (value "Schottky MicroCom 1N5817-TP")
      (footprint "eagle-import:DO41-7.6")
      (fields (field (name "MFR") "Micro Com.") (field (name "PARTNO") "1N5817-TP"))
      (libsource (lib "eagle-import") (part "DIODE-DO41-7.6"))
    )
    (comp (ref "J2A")
      (value "JST-S2B-PH-KL")
      (footprint "eagle-import:JST_S2B_PH_KL")
      (fields (field (name "MFR") "JST") (field (name "PARTNO") "JST_S2B_PH_KL"))
      (libsource (lib "eagle-import") (part "CON_JST_PH_2PINJST_S2B_PH_KL"))
    )
    (comp (ref "U2B")
      (value "MIC2951-03YN 5V, 1.24V-29V, 150ma")
      (footprint "eagle-import:DIL08")
      (fields (field (name "MFR") "Micrel") (field (name "PARTNO") "MIC2951-03YN"))
      (libsource (lib "eagle-import") (part "MIC2951-03YNCN"))
    )
    (comp (ref "R2A")
      (value "170K")
      (footprint "eagle-import:0204_7")
      (fields (field (name "MFR") "Yageo") (field (name "PARTNO") "MFR-25FBF52-169K"))
      (libsource (lib "eagle-import") (part "R-US_0204/7"))
    )
  )
  (nets
    (net (code "1") (name "B0") (class "Default")
      (node (ref "J4") (pin "4") (pinfunction "4_4") (pintype "bidirectional"))
      (node (ref "U1") (pin "5") (pinfunction "(MOSI/DI/SDA/AIN0/OC0A/OC1AN/AREF/PCINT0)PB0_5") (pintype "bidirectional"))
    )
    (net (code "2") (name "B1") (class "Default")
      (node (ref "J4") (pin "3") (pinfunction "3_3") (pintype "bidirectional"))
      (node (ref "R6") (pin "1") (pinfunction "1_1") (pintype "passive"))
      (node (ref "U1") (pin "6") (pinfunction "(MISO/DO/AIN1/OC0B/OC1A/PCINT1)PB1_6") (pintype "bidirectional"))
    )
    (net (code "3") (name "B2") (class "Default")
      (node (ref "J4") (pin "2") (pinfunction "2_2") (pintype "bidirectional"))
      (node (ref "U1") (pin "7") (pinfunction "(SCK/USCK/SCL/ADC1/T0/INT0/PCINT2)PB2_7") (pintype "bidirectional"))
    )
    (net (code "4") (name "B3") (class "Default")
      (node (ref "J3") (pin "2") (pinfunction "2_2") (pintype "bidirectional"))
      (node (ref "R5") (pin "1") (pinfunction "1_1") (pintype "passive"))
      (node (ref "U1") (pin "2") (pinfunction "(XTAL1/CLKI/OC1BN/ADC3/PCINT3)PB3_2") (pintype "bidirectional"))
    )
    (net (code "5") (name "B4") (class "Default")
      (node (ref "J3") (pin "3") (pinfunction "3_3") (pintype "bidirectional"))
      (node (ref "R4") (pin "1") (pinfunction "1_1") (pintype "passive"))
      (node (ref "U1") (pin "3") (pinfunction "(XTAL2/CLKO/OC1B/ADC2/PCINT4)PB4_3") (pintype "bidirectional"))
    )
    (net (code "6") (name "D+") (class "Default")
      (node (ref "D3") (pin "C") (pinfunction "C_C") (pintype "passive"))
      (node (ref "J1") (pin "3") (pinfunction "3_3") (pintype "passive"))
      (node (ref "R4") (pin "2") (pinfunction "2_2") (pintype "passive"))
    )
    (net (code "7") (name "D-") (class "Default")
      (node (ref "D4") (pin "C") (pinfunction "C_C") (pintype "passive"))
      (node (ref "J1") (pin "2") (pinfunction "2_2") (pintype "passive"))
      (node (ref "R5") (pin "2") (pinfunction "2_2") (pintype "passive"))
      (node (ref "R7") (pin "2") (pinfunction "2_2") (pintype "passive"))
    )
    (net (code "8") (name "GND") (class "Default")
      (node (ref "C1") (pin "2") (pinfunction "2_2") (pintype "passive"))
      (node (ref "C1A") (pin "2") (pinfunction "2_2") (pintype "passive"))
      (node (ref "C1B") (pin "2") (pinfunction "2_2") (pintype "passive"))
      (node (ref "C3") (pin "2") (pinfunction "2_2") (pintype "passive"))
      (node (ref "D3") (pin "A") (pinfunction "A_A") (pintype "passive"))
      (node (ref "D4") (pin "A") (pinfunction "A_A") (pintype "passive"))
      (node (ref "J1") (pin "5") (pinfunction "5_5") (pintype "passive"))
      (node (ref "J2") (pin "2") (pinfunction "2_2") (pintype "passive"))
      (node (ref "J2A") (pin "2") (pinfunction "2_2") (pintype "passive"))
      (node (ref "J3") (pin "4") (pinfunction "4_4") (pintype "bidirectional"))
      (node (ref "LED1") (pin "K") (pinfunction "C_K") (pintype "passive"))
      (node (ref "LED2") (pin "K") (pinfunction "C_K") (pintype "passive"))
      (node (ref "R1") (pin "1") (pinfunction "1_1") (pintype "passive"))
      (node (ref "R1A") (pin "1") (pinfunction "1_1") (pintype "passive"))
      (node (ref "S1") (pin "1") (pinfunction "S_1") (pintype "passive"))
      (node (ref "S1") (pin "2") (pinfunction "S1_2") (pintype "passive"))
      (node (ref "U1") (pin "4") (pinfunction "GND_4") (pintype "bidirectional"))
      (node (ref "U2") (pin "4") (pinfunction "GND_4") (pintype "power_in"))
      (node (ref "U2A") (pin "4") (pinfunction "GND_4") (pintype "power_in"))
      (node (ref "U2B") (pin "4") (pinfunction "GND_4") (pintype "power_in"))
    )
    (net (code "9") (name "Net-(LED1-PadA)") (class "Default")
      (node (ref "LED1") (pin "A") (pinfunction "A_A") (pintype "passive"))
      (node (ref "R6") (pin "2") (pinfunction "2_2") (pintype "passive"))
    )
    (net (code "10") (name "Net-(LED2-PadA)") (class "Default")
      (node (ref "LED2") (pin "A") (pinfunction "A_A") (pintype "passive"))
      (node (ref "R3") (pin "1") (pinfunction "1_1") (pintype "passive"))
    )
    (net (code "11") (name "RESETN") (class "Default")
      (node (ref "J3") (pin "1") (pinfunction "1_1") (pintype "bidirectional"))
      (node (ref "S1") (pin "3") (pinfunction "P_3") (pintype "passive"))
      (node (ref "S1") (pin "4") (pinfunction "P1_4") (pintype "passive"))
      (node (ref "U1") (pin "1") (pinfunction "(RESETN/DW/ADC0/PCINT5)PB5_1") (pintype "bidirectional"))
    )
    (net (code "12") (name "VBAT") (class "Default")
      (node (ref "D1") (pin "A") (pinfunction "A_A") (pintype "passive"))
      (node (ref "D1A") (pin "A") (pinfunction "A_A") (pintype "passive"))
      (node (ref "D5") (pin "A") (pinfunction "A_A") (pintype "passive"))
      (node (ref "J2") (pin "1") (pinfunction "1_1") (pintype "passive"))
      (node (ref "J2A") (pin "1") (pinfunction "1_1") (pintype "passive"))
      (node (ref "J5") (pin "1") (pinfunction "1_1") (pintype "passive"))
    )
    (net (code "13") (name "VBUS") (class "Default")
      (node (ref "D2") (pin "A") (pinfunction "A_A") (pintype "passive"))
      (node (ref "D2A") (pin "A") (pinfunction "A_A") (pintype "passive"))
      (node (ref "D2B") (pin "A") (pinfunction "A_A") (pintype "passive"))
      (node (ref "J1") (pin "1") (pinfunction "1_1") (pintype "passive"))
      (node (ref "J6") (pin "1") (pinfunction "1_1") (pintype "passive"))
    )
    (net (code "14") (name "VCC") (class "Default")
      (node (ref "C2") (pin "1") (pinfunction "1_1") (pintype "passive"))
      (node (ref "C2A") (pin "1") (pinfunction "1_1") (pintype "passive"))
      (node (ref "C3") (pin "1") (pinfunction "1_1") (pintype "passive"))
      (node (ref "D5") (pin "C") (pinfunction "C_C") (pintype "passive"))
      (node (ref "J4") (pin "1") (pinfunction "1_1") (pintype "bidirectional"))
      (node (ref "R2") (pin "2") (pinfunction "2_2") (pintype "passive"))
      (node (ref "R2A") (pin "2") (pinfunction "2_2") (pintype "passive"))
      (node (ref "R2B") (pin "2") (pinfunction "2_2") (pintype "passive"))
      (node (ref "R3") (pin "2") (pinfunction "2_2") (pintype "passive"))
      (node (ref "R7") (pin "1") (pinfunction "1_1") (pintype "passive"))
      (node (ref "U1") (pin "8") (pinfunction "VCC_8") (pintype "bidirectional"))
      (node (ref "U2") (pin "1") (pinfunction "OUT_1") (pintype "output"))
      (node (ref "U2A") (pin "1") (pinfunction "OUT_1") (pintype "output"))
      (node (ref "U2B") (pin "1") (pinfunction "OUT_1") (pintype "output"))
      (node (ref "U2B") (pin "2") (pinfunction "SENSE_2") (pintype "input"))
    )
    (net (code "15") (name "VFB") (class "Default")
      (node (ref "C2") (pin "2") (pinfunction "2_2") (pintype "passive"))
      (node (ref "C2A") (pin "2") (pinfunction "2_2") (pintype "passive"))
      (node (ref "R1") (pin "2") (pinfunction "2_2") (pintype "passive"))
      (node (ref "R1A") (pin "2") (pinfunction "2_2") (pintype "passive"))
      (node (ref "R2") (pin "1") (pinfunction "1_1") (pintype "passive"))
      (node (ref "R2A") (pin "1") (pinfunction "1_1") (pintype "passive"))
      (node (ref "R2B") (pin "1") (pinfunction "1_1") (pintype "passive"))
      (node (ref "U2") (pin "7") (pinfunction "FEEDB_7") (pintype "output"))
      (node (ref "U2A") (pin "7") (pinfunction "FEEDB_7") (pintype "output"))
      (node (ref "U2B") (pin "6") (pinfunction "VTAB_6") (pintype "input"))
      (node (ref "U2B") (pin "7") (pinfunction "FEEDB_7") (pintype "output"))
    )
    (net (code "16") (name "VIN") (class "Default")
      (node (ref "C1") (pin "1") (pinfunction "1_1") (pintype "passive"))
      (node (ref "C1A") (pin "1") (pinfunction "1_1") (pintype "passive"))
      (node (ref "C1B") (pin "1") (pinfunction "1_1") (pintype "passive"))
      (node (ref "D1") (pin "C") (pinfunction "C_C") (pintype "passive"))
      (node (ref "D1A") (pin "C") (pinfunction "C_C") (pintype "passive"))
      (node (ref "D2") (pin "C") (pinfunction "C_C") (pintype "passive"))
      (node (ref "D2A") (pin "C") (pinfunction "C_C") (pintype "passive"))
      (node (ref "U2") (pin "8") (pinfunction "INPUT_8") (pintype "passive"))
      (node (ref "U2A") (pin "8") (pinfunction "INPUT_8") (pintype "passive"))
      (node (ref "U2B") (pin "8") (pinfunction "INPUT_8") (pintype "passive"))
    )
    (net (code "17") (name "unconnected-(D2B-PadC)") (class "Default")
      (node (ref "D2B") (pin "C") (pinfunction "C_C") (pintype "passive"))
    )
    (net (code "18") (name "unconnected-(J1-Pad4)") (class "Default")
      (node (ref "J1") (pin "4") (pinfunction "4_4") (pintype "passive"))
    )
    (net (code "19") (name "unconnected-(U2-ERROR-Pad5)") (class "Default")
      (node (ref "U2") (pin "5") (pinfunction "ERROR_5") (pintype "output"))
    )
    (net (code "20") (name "unconnected-(U2-SENSE-Pad2)") (class "Default")
      (node (ref "U2") (pin "2") (pinfunction "SENSE_2") (pintype "input"))
    )
    (net (code "21") (name "unconnected-(U2-SHDN-Pad3)") (class "Default")
      (node (ref "U2") (pin "3") (pinfunction "SHDN_3") (pintype "input"))
    )
    (net (code "22") (name "unconnected-(U2-VTAB-Pad6)") (class "Default")
      (node (ref "U2") (pin "6") (pinfunction "VTAB_6") (pintype "input"))
    )
    (net (code "23") (name "unconnected-(U2A-ERROR-Pad5)") (class "Default")
      (node (ref "U2A") (pin "5") (pinfunction "ERROR_5") (pintype "output"))
    )
    (net (code "24") (name "unconnected-(U2A-SENSE-Pad2)") (class "Default")
      (node (ref "U2A") (pin "2") (pinfunction "SENSE_2") (pintype "input"))
    )
    (net (code "25") (name "unconnected-(U2A-SHDN-Pad3)") (class "Default")
      (node (ref "U2A") (pin "3") (pinfunction "SHDN_3") (pintype "input"))
    )
    (net (code "26") (name "unconnected-(U2A-VTAB-Pad6)") (class "Default")
      (node (ref "U2A") (pin "6") (pinfunction "VTAB_6") (pintype "input"))
    )
    (net (code "27") (name "unconnected-(U2B-ERROR-Pad5)") (class "Default")
      (node (ref "U2B") (pin "5") (pinfunction "ERROR_5") (pintype "output"))
    )
    (net (code "28") (name "unconnected-(U2B-SHDN-Pad3)") (class "Default")
      (node (ref "U2B") (pin "3") (pinfunction "SHDN_3") (pintype "input"))
    )
  )
)
